# 03_RK3399_Power.net
KiCad netlist of a schematic drawn in Altium Designer
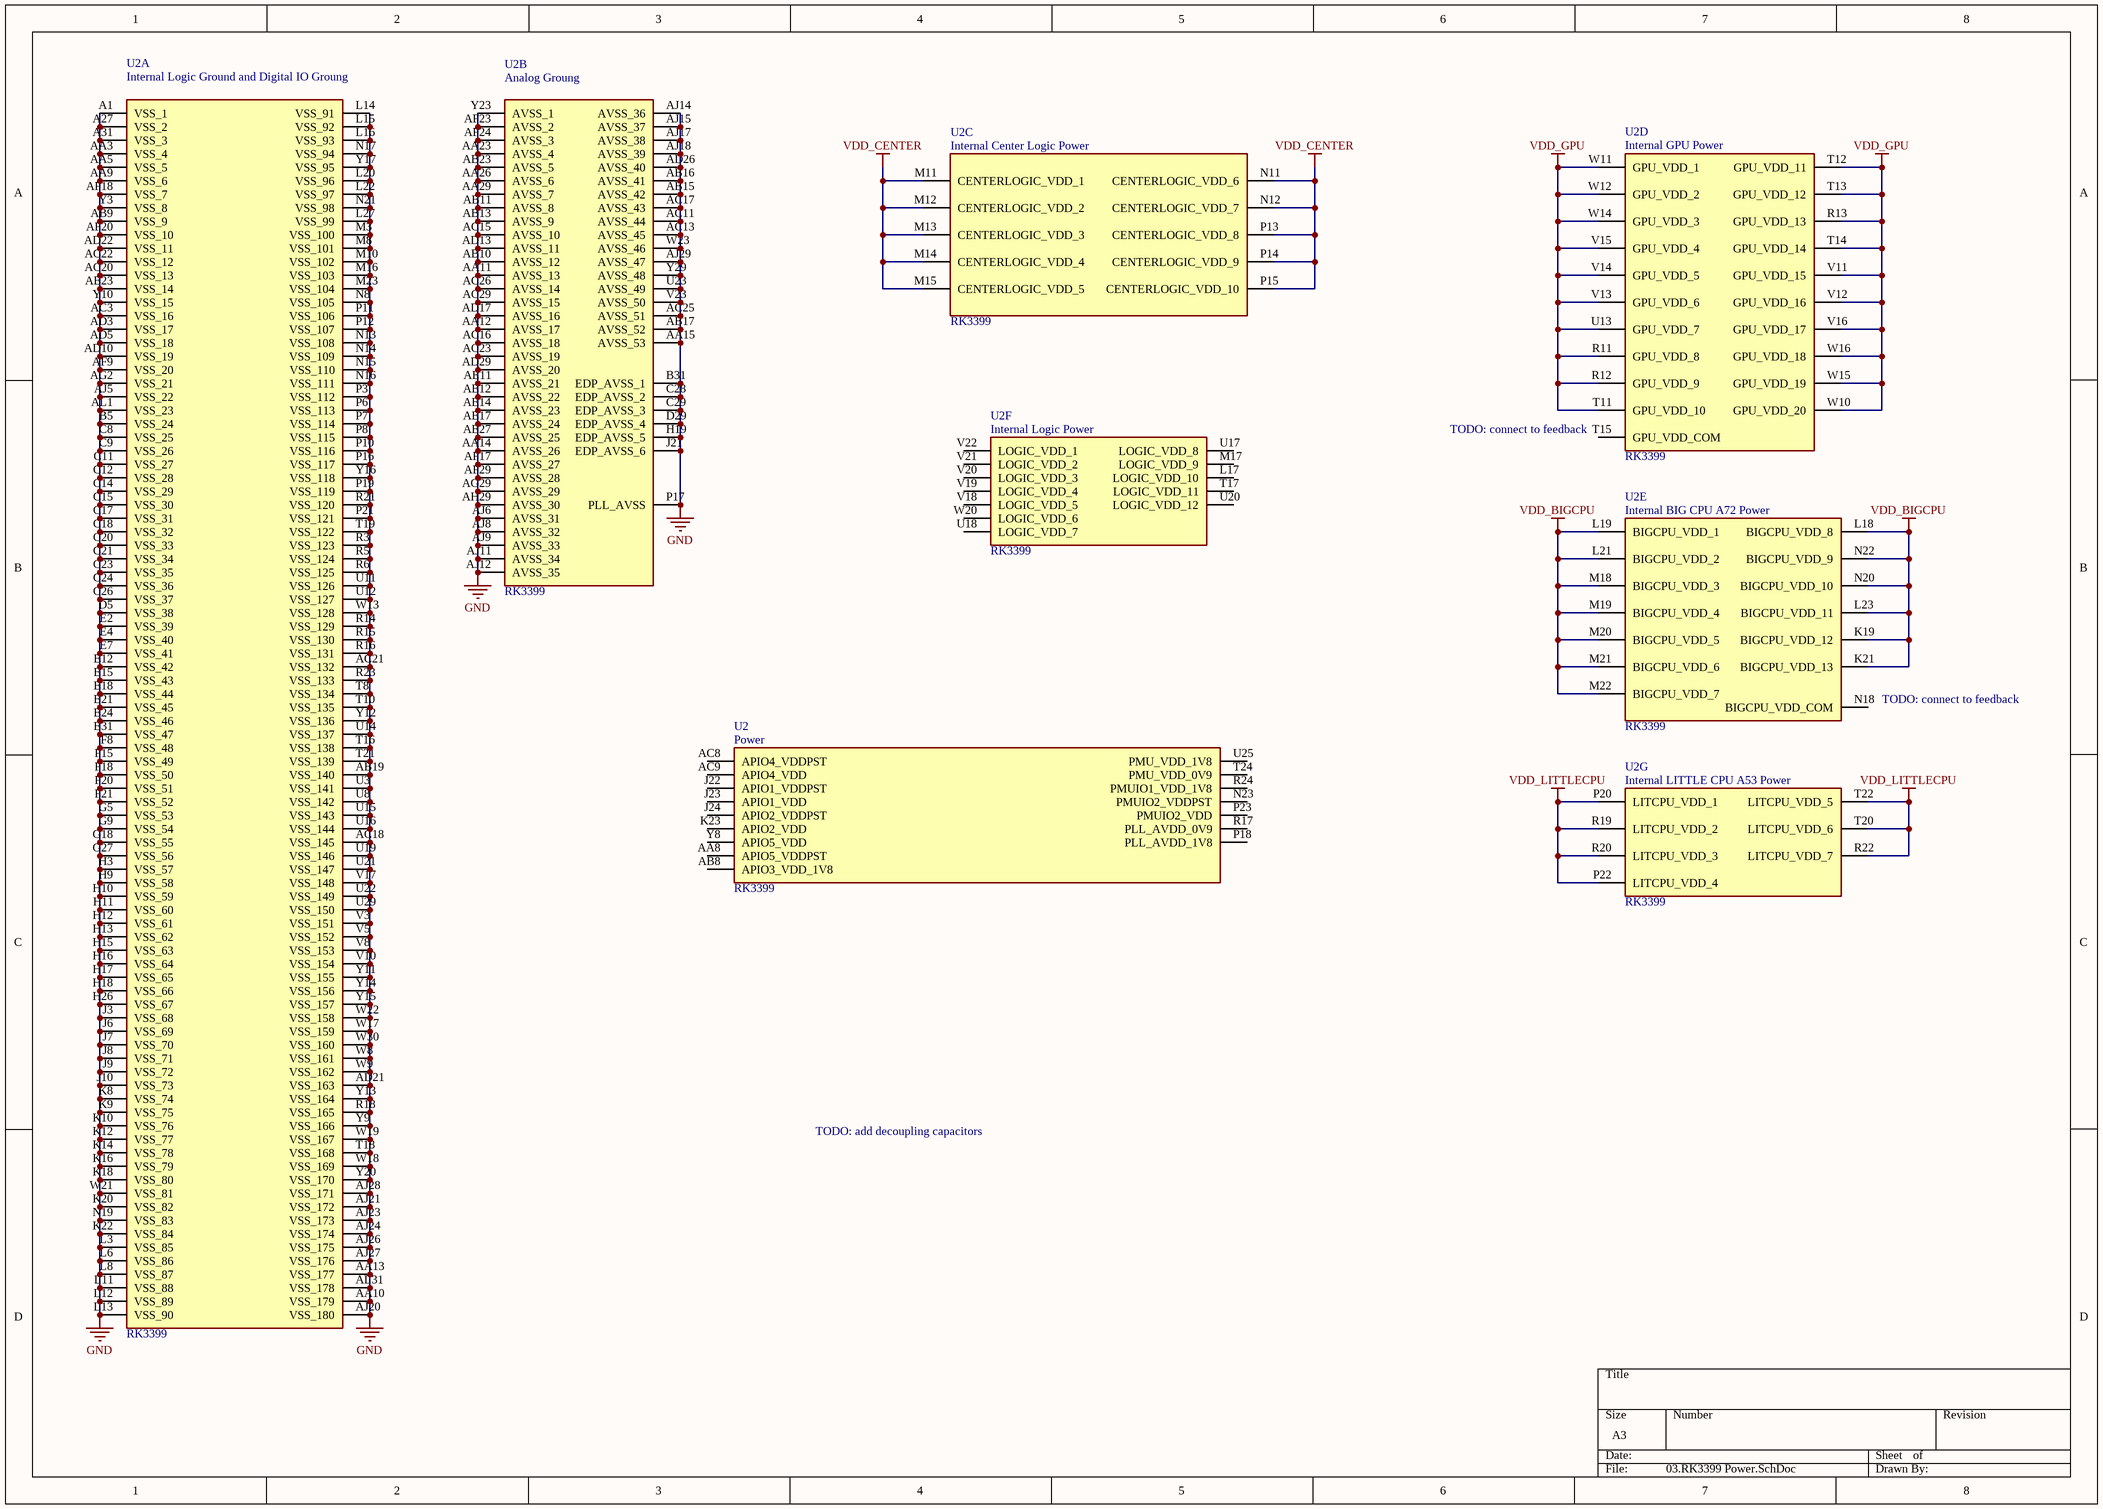
[diagram p0: 03.RK3399 Power.SchDoc]

(export (version "E")
  (design (tool "Eeschema 10.0.6"))
  (components
    (comp (ref "U2")
      (value "RK3399")
      (footprint "BGA828C65P31X31_2100X2100X161N")
      (description "RK3399 ROCK Pi 4 Model A 2GB - ARMÂ® CortexÂ®-A53, CortexÂ®-A72 MPU Embedded Evaluation Board")
      (fields (field (name "MF") "Rockchip"))
      (libsource (lib "RK3399") (part "RK3399"))
    )
  )
  (nets
    (net (code "1") (name "GND") (class "Default")
      (node (ref "U2") (pin "A1") (pinfunction "VSS_1_A1") (pintype "power_in"))
      (node (ref "U2") (pin "A27") (pinfunction "VSS_2_A27") (pintype "power_in"))
      (node (ref "U2") (pin "A31") (pinfunction "VSS_3_A31") (pintype "power_in"))
      (node (ref "U2") (pin "AA10") (pinfunction "VSS_179_AA10") (pintype "power_in"))
      (node (ref "U2") (pin "AA11") (pinfunction "AVSS_13_AA11") (pintype "power_in"))
      (node (ref "U2") (pin "AA12") (pinfunction "AVSS_17_AA12") (pintype "power_in"))
      (node (ref "U2") (pin "AA13") (pinfunction "VSS_177_AA13") (pintype "power_in"))
      (node (ref "U2") (pin "AA14") (pinfunction "AVSS_26_AA14") (pintype "power_in"))
      (node (ref "U2") (pin "AA15") (pinfunction "AVSS_53_AA15") (pintype "power_in"))
      (node (ref "U2") (pin "AA23") (pinfunction "AVSS_4_AA23") (pintype "power_in"))
      (node (ref "U2") (pin "AA26") (pinfunction "AVSS_6_AA26") (pintype "power_in"))
      (node (ref "U2") (pin "AA29") (pinfunction "AVSS_7_AA29") (pintype "power_in"))
      (node (ref "U2") (pin "AA3") (pinfunction "VSS_4_AA3") (pintype "power_in"))
      (node (ref "U2") (pin "AA5") (pinfunction "VSS_5_AA5") (pintype "power_in"))
      (node (ref "U2") (pin "AA9") (pinfunction "VSS_6_AA9") (pintype "power_in"))
      (node (ref "U2") (pin "AB10") (pinfunction "AVSS_12_AB10") (pintype "power_in"))
      (node (ref "U2") (pin "AB11") (pinfunction "AVSS_8_AB11") (pintype "power_in"))
      (node (ref "U2") (pin "AB13") (pinfunction "AVSS_9_AB13") (pintype "power_in"))
      (node (ref "U2") (pin "AB15") (pinfunction "AVSS_42_AB15") (pintype "power_in"))
      (node (ref "U2") (pin "AB16") (pinfunction "AVSS_41_AB16") (pintype "power_in"))
      (node (ref "U2") (pin "AB17") (pinfunction "AVSS_52_AB17") (pintype "power_in"))
      (node (ref "U2") (pin "AB19") (pinfunction "VSS_140_AB19") (pintype "power_in"))
      (node (ref "U2") (pin "AB23") (pinfunction "AVSS_5_AB23") (pintype "power_in"))
      (node (ref "U2") (pin "AB9") (pinfunction "VSS_9_AB9") (pintype "power_in"))
      (node (ref "U2") (pin "AC11") (pinfunction "AVSS_44_AC11") (pintype "power_in"))
      (node (ref "U2") (pin "AC13") (pinfunction "AVSS_45_AC13") (pintype "power_in"))
      (node (ref "U2") (pin "AC15") (pinfunction "AVSS_10_AC15") (pintype "power_in"))
      (node (ref "U2") (pin "AC16") (pinfunction "AVSS_18_AC16") (pintype "power_in"))
      (node (ref "U2") (pin "AC17") (pinfunction "AVSS_43_AC17") (pintype "power_in"))
      (node (ref "U2") (pin "AC18") (pinfunction "VSS_145_AC18") (pintype "power_in"))
      (node (ref "U2") (pin "AC20") (pinfunction "VSS_13_AC20") (pintype "power_in"))
      (node (ref "U2") (pin "AC21") (pinfunction "VSS_132_AC21") (pintype "power_in"))
      (node (ref "U2") (pin "AC22") (pinfunction "VSS_12_AC22") (pintype "power_in"))
      (node (ref "U2") (pin "AC23") (pinfunction "AVSS_19_AC23") (pintype "power_in"))
      (node (ref "U2") (pin "AC25") (pinfunction "AVSS_51_AC25") (pintype "power_in"))
      (node (ref "U2") (pin "AC26") (pinfunction "AVSS_14_AC26") (pintype "power_in"))
      (node (ref "U2") (pin "AC29") (pinfunction "AVSS_15_AC29") (pintype "power_in"))
      (node (ref "U2") (pin "AC3") (pinfunction "VSS_16_AC3") (pintype "power_in"))
      (node (ref "U2") (pin "AD10") (pinfunction "VSS_19_AD10") (pintype "power_in"))
      (node (ref "U2") (pin "AD13") (pinfunction "AVSS_11_AD13") (pintype "power_in"))
      (node (ref "U2") (pin "AD17") (pinfunction "AVSS_16_AD17") (pintype "power_in"))
      (node (ref "U2") (pin "AD21") (pinfunction "VSS_163_AD21") (pintype "power_in"))
      (node (ref "U2") (pin "AD22") (pinfunction "VSS_11_AD22") (pintype "power_in"))
      (node (ref "U2") (pin "AD26") (pinfunction "AVSS_40_AD26") (pintype "power_in"))
      (node (ref "U2") (pin "AD29") (pinfunction "AVSS_20_AD29") (pintype "power_in"))
      (node (ref "U2") (pin "AD3") (pinfunction "VSS_17_AD3") (pintype "power_in"))
      (node (ref "U2") (pin "AD5") (pinfunction "VSS_18_AD5") (pintype "power_in"))
      (node (ref "U2") (pin "AE11") (pinfunction "AVSS_21_AE11") (pintype "power_in"))
      (node (ref "U2") (pin "AE12") (pinfunction "AVSS_22_AE12") (pintype "power_in"))
      (node (ref "U2") (pin "AE14") (pinfunction "AVSS_23_AE14") (pintype "power_in"))
      (node (ref "U2") (pin "AE17") (pinfunction "AVSS_24_AE17") (pintype "power_in"))
      (node (ref "U2") (pin "AE23") (pinfunction "VSS_14_AE23") (pintype "power_in"))
      (node (ref "U2") (pin "AE27") (pinfunction "AVSS_25_AE27") (pintype "power_in"))
      (node (ref "U2") (pin "AF17") (pinfunction "AVSS_27_AF17") (pintype "power_in"))
      (node (ref "U2") (pin "AF18") (pinfunction "VSS_7_AF18") (pintype "power_in"))
      (node (ref "U2") (pin "AF20") (pinfunction "VSS_10_AF20") (pintype "power_in"))
      (node (ref "U2") (pin "AF23") (pinfunction "AVSS_2_AF23") (pintype "power_in"))
      (node (ref "U2") (pin "AF24") (pinfunction "AVSS_3_AF24") (pintype "power_in"))
      (node (ref "U2") (pin "AF29") (pinfunction "AVSS_28_AF29") (pintype "power_in"))
      (node (ref "U2") (pin "AF9") (pinfunction "VSS_20_AF9") (pintype "power_in"))
      (node (ref "U2") (pin "AG2") (pinfunction "VSS_21_AG2") (pintype "power_in"))
      (node (ref "U2") (pin "AG29") (pinfunction "AVSS_29_AG29") (pintype "power_in"))
      (node (ref "U2") (pin "AH29") (pinfunction "AVSS_30_AH29") (pintype "power_in"))
      (node (ref "U2") (pin "AJ11") (pinfunction "AVSS_34_AJ11") (pintype "power_in"))
      (node (ref "U2") (pin "AJ12") (pinfunction "AVSS_35_AJ12") (pintype "power_in"))
      (node (ref "U2") (pin "AJ14") (pinfunction "AVSS_36_AJ14") (pintype "power_in"))
      (node (ref "U2") (pin "AJ15") (pinfunction "AVSS_37_AJ15") (pintype "power_in"))
      (node (ref "U2") (pin "AJ17") (pinfunction "AVSS_38_AJ17") (pintype "power_in"))
      (node (ref "U2") (pin "AJ18") (pinfunction "AVSS_39_AJ18") (pintype "power_in"))
      (node (ref "U2") (pin "AJ20") (pinfunction "VSS_180_AJ20") (pintype "power_in"))
      (node (ref "U2") (pin "AJ21") (pinfunction "VSS_172_AJ21") (pintype "power_in"))
      (node (ref "U2") (pin "AJ23") (pinfunction "VSS_173_AJ23") (pintype "power_in"))
      (node (ref "U2") (pin "AJ24") (pinfunction "VSS_174_AJ24") (pintype "power_in"))
      (node (ref "U2") (pin "AJ26") (pinfunction "VSS_175_AJ26") (pintype "power_in"))
      (node (ref "U2") (pin "AJ27") (pinfunction "VSS_176_AJ27") (pintype "power_in"))
      (node (ref "U2") (pin "AJ28") (pinfunction "VSS_171_AJ28") (pintype "power_in"))
      (node (ref "U2") (pin "AJ29") (pinfunction "AVSS_47_AJ29") (pintype "power_in"))
      (node (ref "U2") (pin "AJ5") (pinfunction "VSS_22_AJ5") (pintype "power_in"))
      (node (ref "U2") (pin "AJ6") (pinfunction "AVSS_31_AJ6") (pintype "power_in"))
      (node (ref "U2") (pin "AJ8") (pinfunction "AVSS_32_AJ8") (pintype "power_in"))
      (node (ref "U2") (pin "AJ9") (pinfunction "AVSS_33_AJ9") (pintype "power_in"))
      (node (ref "U2") (pin "AL1") (pinfunction "VSS_23_AL1") (pintype "power_in"))
      (node (ref "U2") (pin "AL31") (pinfunction "VSS_178_AL31") (pintype "power_in"))
      (node (ref "U2") (pin "B31") (pinfunction "EDP_AVSS_1_B31") (pintype "power_in"))
      (node (ref "U2") (pin "B5") (pinfunction "VSS_24_B5") (pintype "power_in"))
      (node (ref "U2") (pin "C11") (pinfunction "VSS_27_C11") (pintype "power_in"))
      (node (ref "U2") (pin "C12") (pinfunction "VSS_28_C12") (pintype "power_in"))
      (node (ref "U2") (pin "C14") (pinfunction "VSS_29_C14") (pintype "power_in"))
      (node (ref "U2") (pin "C15") (pinfunction "VSS_30_C15") (pintype "power_in"))
      (node (ref "U2") (pin "C17") (pinfunction "VSS_31_C17") (pintype "power_in"))
      (node (ref "U2") (pin "C18") (pinfunction "VSS_32_C18") (pintype "power_in"))
      (node (ref "U2") (pin "C20") (pinfunction "VSS_33_C20") (pintype "power_in"))
      (node (ref "U2") (pin "C21") (pinfunction "VSS_34_C21") (pintype "power_in"))
      (node (ref "U2") (pin "C23") (pinfunction "VSS_35_C23") (pintype "power_in"))
      (node (ref "U2") (pin "C24") (pinfunction "VSS_36_C24") (pintype "power_in"))
      (node (ref "U2") (pin "C26") (pinfunction "VSS_37_C26") (pintype "power_in"))
      (node (ref "U2") (pin "C28") (pinfunction "EDP_AVSS_2_C28") (pintype "power_in"))
      (node (ref "U2") (pin "C29") (pinfunction "EDP_AVSS_3_C29") (pintype "power_in"))
      (node (ref "U2") (pin "C8") (pinfunction "VSS_25_C8") (pintype "power_in"))
      (node (ref "U2") (pin "C9") (pinfunction "VSS_26_C9") (pintype "power_in"))
      (node (ref "U2") (pin "D29") (pinfunction "EDP_AVSS_4_D29") (pintype "power_in"))
      (node (ref "U2") (pin "D5") (pinfunction "VSS_38_D5") (pintype "power_in"))
      (node (ref "U2") (pin "E12") (pinfunction "VSS_42_E12") (pintype "power_in"))
      (node (ref "U2") (pin "E15") (pinfunction "VSS_43_E15") (pintype "power_in"))
      (node (ref "U2") (pin "E18") (pinfunction "VSS_44_E18") (pintype "power_in"))
      (node (ref "U2") (pin "E2") (pinfunction "VSS_39_E2") (pintype "power_in"))
      (node (ref "U2") (pin "E21") (pinfunction "VSS_45_E21") (pintype "power_in"))
      (node (ref "U2") (pin "E24") (pinfunction "VSS_46_E24") (pintype "power_in"))
      (node (ref "U2") (pin "E31") (pinfunction "VSS_47_E31") (pintype "power_in"))
      (node (ref "U2") (pin "E4") (pinfunction "VSS_40_E4") (pintype "power_in"))
      (node (ref "U2") (pin "E7") (pinfunction "VSS_41_E7") (pintype "power_in"))
      (node (ref "U2") (pin "F15") (pinfunction "VSS_49_F15") (pintype "power_in"))
      (node (ref "U2") (pin "F18") (pinfunction "VSS_50_F18") (pintype "power_in"))
      (node (ref "U2") (pin "F20") (pinfunction "VSS_51_F20") (pintype "power_in"))
      (node (ref "U2") (pin "F21") (pinfunction "VSS_52_F21") (pintype "power_in"))
      (node (ref "U2") (pin "F8") (pinfunction "VSS_48_F8") (pintype "power_in"))
      (node (ref "U2") (pin "G18") (pinfunction "VSS_55_G18") (pintype "power_in"))
      (node (ref "U2") (pin "G27") (pinfunction "VSS_56_G27") (pintype "power_in"))
      (node (ref "U2") (pin "G5") (pinfunction "VSS_53_G5") (pintype "power_in"))
      (node (ref "U2") (pin "G9") (pinfunction "VSS_54_G9") (pintype "power_in"))
      (node (ref "U2") (pin "H10") (pinfunction "VSS_59_H10") (pintype "power_in"))
      (node (ref "U2") (pin "H11") (pinfunction "VSS_60_H11") (pintype "power_in"))
      (node (ref "U2") (pin "H12") (pinfunction "VSS_61_H12") (pintype "power_in"))
      (node (ref "U2") (pin "H13") (pinfunction "VSS_62_H13") (pintype "power_in"))
      (node (ref "U2") (pin "H15") (pinfunction "VSS_63_H15") (pintype "power_in"))
      (node (ref "U2") (pin "H16") (pinfunction "VSS_64_H16") (pintype "power_in"))
      (node (ref "U2") (pin "H17") (pinfunction "VSS_65_H17") (pintype "power_in"))
      (node (ref "U2") (pin "H18") (pinfunction "VSS_66_H18") (pintype "power_in"))
      (node (ref "U2") (pin "H19") (pinfunction "EDP_AVSS_5_H19") (pintype "power_in"))
      (node (ref "U2") (pin "H26") (pinfunction "VSS_67_H26") (pintype "power_in"))
      (node (ref "U2") (pin "H3") (pinfunction "VSS_57_H3") (pintype "power_in"))
      (node (ref "U2") (pin "H9") (pinfunction "VSS_58_H9") (pintype "power_in"))
      (node (ref "U2") (pin "J10") (pinfunction "VSS_73_J10") (pintype "power_in"))
      (node (ref "U2") (pin "J21") (pinfunction "EDP_AVSS_6_J21") (pintype "power_in"))
      (node (ref "U2") (pin "J3") (pinfunction "VSS_68_J3") (pintype "power_in"))
      (node (ref "U2") (pin "J6") (pinfunction "VSS_69_J6") (pintype "power_in"))
      (node (ref "U2") (pin "J7") (pinfunction "VSS_70_J7") (pintype "power_in"))
      (node (ref "U2") (pin "J8") (pinfunction "VSS_71_J8") (pintype "power_in"))
      (node (ref "U2") (pin "J9") (pinfunction "VSS_72_J9") (pintype "power_in"))
      (node (ref "U2") (pin "K10") (pinfunction "VSS_76_K10") (pintype "power_in"))
      (node (ref "U2") (pin "K12") (pinfunction "VSS_77_K12") (pintype "power_in"))
      (node (ref "U2") (pin "K14") (pinfunction "VSS_78_K14") (pintype "power_in"))
      (node (ref "U2") (pin "K16") (pinfunction "VSS_79_K16") (pintype "power_in"))
      (node (ref "U2") (pin "K18") (pinfunction "VSS_80_K18") (pintype "power_in"))
      (node (ref "U2") (pin "K20") (pinfunction "VSS_82_K20") (pintype "power_in"))
      (node (ref "U2") (pin "K22") (pinfunction "VSS_84_K22") (pintype "power_in"))
      (node (ref "U2") (pin "K8") (pinfunction "VSS_74_K8") (pintype "power_in"))
      (node (ref "U2") (pin "K9") (pinfunction "VSS_75_K9") (pintype "power_in"))
      (node (ref "U2") (pin "L11") (pinfunction "VSS_88_L11") (pintype "power_in"))
      (node (ref "U2") (pin "L12") (pinfunction "VSS_89_L12") (pintype "power_in"))
      (node (ref "U2") (pin "L13") (pinfunction "VSS_90_L13") (pintype "power_in"))
      (node (ref "U2") (pin "L14") (pinfunction "VSS_91_L14") (pintype "power_in"))
      (node (ref "U2") (pin "L15") (pinfunction "VSS_92_L15") (pintype "power_in"))
      (node (ref "U2") (pin "L16") (pinfunction "VSS_93_L16") (pintype "power_in"))
      (node (ref "U2") (pin "L20") (pinfunction "VSS_96_L20") (pintype "power_in"))
      (node (ref "U2") (pin "L22") (pinfunction "VSS_97_L22") (pintype "power_in"))
      (node (ref "U2") (pin "L27") (pinfunction "VSS_99_L27") (pintype "power_in"))
      (node (ref "U2") (pin "L3") (pinfunction "VSS_85_L3") (pintype "power_in"))
      (node (ref "U2") (pin "L6") (pinfunction "VSS_86_L6") (pintype "power_in"))
      (node (ref "U2") (pin "L8") (pinfunction "VSS_87_L8") (pintype "power_in"))
      (node (ref "U2") (pin "M10") (pinfunction "VSS_102_M10") (pintype "power_in"))
      (node (ref "U2") (pin "M16") (pinfunction "VSS_103_M16") (pintype "power_in"))
      (node (ref "U2") (pin "M23") (pinfunction "VSS_104_M23") (pintype "power_in"))
      (node (ref "U2") (pin "M3") (pinfunction "VSS_100_M3") (pintype "power_in"))
      (node (ref "U2") (pin "M8") (pinfunction "VSS_101_M8") (pintype "power_in"))
      (node (ref "U2") (pin "N13") (pinfunction "VSS_108_N13") (pintype "power_in"))
      (node (ref "U2") (pin "N14") (pinfunction "VSS_109_N14") (pintype "power_in"))
      (node (ref "U2") (pin "N15") (pinfunction "VSS_110_N15") (pintype "power_in"))
      (node (ref "U2") (pin "N16") (pinfunction "VSS_111_N16") (pintype "power_in"))
      (node (ref "U2") (pin "N17") (pinfunction "VSS_94_N17") (pintype "power_in"))
      (node (ref "U2") (pin "N19") (pinfunction "VSS_83_N19") (pintype "power_in"))
      (node (ref "U2") (pin "N21") (pinfunction "VSS_98_N21") (pintype "power_in"))
      (node (ref "U2") (pin "N8") (pinfunction "VSS_105_N8") (pintype "power_in"))
      (node (ref "U2") (pin "P10") (pinfunction "VSS_116_P10") (pintype "power_in"))
      (node (ref "U2") (pin "P11") (pinfunction "VSS_106_P11") (pintype "power_in"))
      (node (ref "U2") (pin "P12") (pinfunction "VSS_107_P12") (pintype "power_in"))
      (node (ref "U2") (pin "P16") (pinfunction "VSS_117_P16") (pintype "power_in"))
      (node (ref "U2") (pin "P17") (pinfunction "PLL_AVSS_P17") (pintype "power_in"))
      (node (ref "U2") (pin "P19") (pinfunction "VSS_119_P19") (pintype "power_in"))
      (node (ref "U2") (pin "P21") (pinfunction "VSS_121_P21") (pintype "power_in"))
      (node (ref "U2") (pin "P3") (pinfunction "VSS_112_P3") (pintype "power_in"))
      (node (ref "U2") (pin "P6") (pinfunction "VSS_113_P6") (pintype "power_in"))
      (node (ref "U2") (pin "P7") (pinfunction "VSS_114_P7") (pintype "power_in"))
      (node (ref "U2") (pin "P8") (pinfunction "VSS_115_P8") (pintype "power_in"))
      (node (ref "U2") (pin "R14") (pinfunction "VSS_129_R14") (pintype "power_in"))
      (node (ref "U2") (pin "R15") (pinfunction "VSS_130_R15") (pintype "power_in"))
      (node (ref "U2") (pin "R16") (pinfunction "VSS_131_R16") (pintype "power_in"))
      (node (ref "U2") (pin "R18") (pinfunction "VSS_165_R18") (pintype "power_in"))
      (node (ref "U2") (pin "R21") (pinfunction "VSS_120_R21") (pintype "power_in"))
      (node (ref "U2") (pin "R23") (pinfunction "VSS_133_R23") (pintype "power_in"))
      (node (ref "U2") (pin "R3") (pinfunction "VSS_123_R3") (pintype "power_in"))
      (node (ref "U2") (pin "R5") (pinfunction "VSS_124_R5") (pintype "power_in"))
      (node (ref "U2") (pin "R6") (pinfunction "VSS_125_R6") (pintype "power_in"))
      (node (ref "U2") (pin "T10") (pinfunction "VSS_135_T10") (pintype "power_in"))
      (node (ref "U2") (pin "T16") (pinfunction "VSS_138_T16") (pintype "power_in"))
      (node (ref "U2") (pin "T18") (pinfunction "VSS_168_T18") (pintype "power_in"))
      (node (ref "U2") (pin "T19") (pinfunction "VSS_122_T19") (pintype "power_in"))
      (node (ref "U2") (pin "T21") (pinfunction "VSS_139_T21") (pintype "power_in"))
      (node (ref "U2") (pin "T8") (pinfunction "VSS_134_T8") (pintype "power_in"))
      (node (ref "U2") (pin "U11") (pinfunction "VSS_126_U11") (pintype "power_in"))
      (node (ref "U2") (pin "U12") (pinfunction "VSS_127_U12") (pintype "power_in"))
      (node (ref "U2") (pin "U14") (pinfunction "VSS_137_U14") (pintype "power_in"))
      (node (ref "U2") (pin "U15") (pinfunction "VSS_143_U15") (pintype "power_in"))
      (node (ref "U2") (pin "U16") (pinfunction "VSS_144_U16") (pintype "power_in"))
      (node (ref "U2") (pin "U19") (pinfunction "VSS_146_U19") (pintype "power_in"))
      (node (ref "U2") (pin "U21") (pinfunction "VSS_147_U21") (pintype "power_in"))
      (node (ref "U2") (pin "U22") (pinfunction "VSS_149_U22") (pintype "power_in"))
      (node (ref "U2") (pin "U23") (pinfunction "AVSS_49_U23") (pintype "power_in"))
      (node (ref "U2") (pin "U29") (pinfunction "VSS_150_U29") (pintype "power_in"))
      (node (ref "U2") (pin "U3") (pinfunction "VSS_141_U3") (pintype "power_in"))
      (node (ref "U2") (pin "U8") (pinfunction "VSS_142_U8") (pintype "power_in"))
      (node (ref "U2") (pin "V10") (pinfunction "VSS_154_V10") (pintype "power_in"))
      (node (ref "U2") (pin "V17") (pinfunction "VSS_148_V17") (pintype "power_in"))
      (node (ref "U2") (pin "V23") (pinfunction "AVSS_50_V23") (pintype "power_in"))
      (node (ref "U2") (pin "V3") (pinfunction "VSS_151_V3") (pintype "power_in"))
      (node (ref "U2") (pin "V5") (pinfunction "VSS_152_V5") (pintype "power_in"))
      (node (ref "U2") (pin "V8") (pinfunction "VSS_153_V8") (pintype "power_in"))
      (node (ref "U2") (pin "W13") (pinfunction "VSS_128_W13") (pintype "power_in"))
      (node (ref "U2") (pin "W17") (pinfunction "VSS_159_W17") (pintype "power_in"))
      (node (ref "U2") (pin "W18") (pinfunction "VSS_169_W18") (pintype "power_in"))
      (node (ref "U2") (pin "W19") (pinfunction "VSS_167_W19") (pintype "power_in"))
      (node (ref "U2") (pin "W21") (pinfunction "VSS_81_W21") (pintype "power_in"))
      (node (ref "U2") (pin "W22") (pinfunction "VSS_158_W22") (pintype "power_in"))
      (node (ref "U2") (pin "W23") (pinfunction "AVSS_46_W23") (pintype "power_in"))
      (node (ref "U2") (pin "W30") (pinfunction "VSS_160_W30") (pintype "power_in"))
      (node (ref "U2") (pin "W8") (pinfunction "VSS_161_W8") (pintype "power_in"))
      (node (ref "U2") (pin "W9") (pinfunction "VSS_162_W9") (pintype "power_in"))
      (node (ref "U2") (pin "Y10") (pinfunction "VSS_15_Y10") (pintype "power_in"))
      (node (ref "U2") (pin "Y11") (pinfunction "VSS_155_Y11") (pintype "power_in"))
      (node (ref "U2") (pin "Y12") (pinfunction "VSS_136_Y12") (pintype "power_in"))
      (node (ref "U2") (pin "Y13") (pinfunction "VSS_164_Y13") (pintype "power_in"))
      (node (ref "U2") (pin "Y14") (pinfunction "VSS_156_Y14") (pintype "power_in"))
      (node (ref "U2") (pin "Y15") (pinfunction "VSS_157_Y15") (pintype "power_in"))
      (node (ref "U2") (pin "Y16") (pinfunction "VSS_118_Y16") (pintype "power_in"))
      (node (ref "U2") (pin "Y17") (pinfunction "VSS_95_Y17") (pintype "power_in"))
      (node (ref "U2") (pin "Y20") (pinfunction "VSS_170_Y20") (pintype "power_in"))
      (node (ref "U2") (pin "Y23") (pinfunction "AVSS_1_Y23") (pintype "power_in"))
      (node (ref "U2") (pin "Y29") (pinfunction "AVSS_48_Y29") (pintype "power_in"))
      (node (ref "U2") (pin "Y3") (pinfunction "VSS_8_Y3") (pintype "power_in"))
      (node (ref "U2") (pin "Y9") (pinfunction "VSS_166_Y9") (pintype "power_in"))
    )
    (net (code "2") (name "VDD_BIGCPU") (class "Default")
      (node (ref "U2") (pin "K19") (pinfunction "BIGCPU_VDD_12_K19") (pintype "power_in"))
      (node (ref "U2") (pin "K21") (pinfunction "BIGCPU_VDD_13_K21") (pintype "power_in"))
      (node (ref "U2") (pin "L18") (pinfunction "BIGCPU_VDD_8_L18") (pintype "power_in"))
      (node (ref "U2") (pin "L19") (pinfunction "BIGCPU_VDD_1_L19") (pintype "power_in"))
      (node (ref "U2") (pin "L21") (pinfunction "BIGCPU_VDD_2_L21") (pintype "power_in"))
      (node (ref "U2") (pin "L23") (pinfunction "BIGCPU_VDD_11_L23") (pintype "power_in"))
      (node (ref "U2") (pin "M18") (pinfunction "BIGCPU_VDD_3_M18") (pintype "power_in"))
      (node (ref "U2") (pin "M19") (pinfunction "BIGCPU_VDD_4_M19") (pintype "power_in"))
      (node (ref "U2") (pin "M20") (pinfunction "BIGCPU_VDD_5_M20") (pintype "power_in"))
      (node (ref "U2") (pin "M21") (pinfunction "BIGCPU_VDD_6_M21") (pintype "power_in"))
      (node (ref "U2") (pin "M22") (pinfunction "BIGCPU_VDD_7_M22") (pintype "power_in"))
      (node (ref "U2") (pin "N20") (pinfunction "BIGCPU_VDD_10_N20") (pintype "power_in"))
      (node (ref "U2") (pin "N22") (pinfunction "BIGCPU_VDD_9_N22") (pintype "power_in"))
    )
    (net (code "3") (name "VDD_CENTER") (class "Default")
      (node (ref "U2") (pin "M11") (pinfunction "CENTERLOGIC_VDD_1_M11") (pintype "power_in"))
      (node (ref "U2") (pin "M12") (pinfunction "CENTERLOGIC_VDD_2_M12") (pintype "power_in"))
      (node (ref "U2") (pin "M13") (pinfunction "CENTERLOGIC_VDD_3_M13") (pintype "power_in"))
      (node (ref "U2") (pin "M14") (pinfunction "CENTERLOGIC_VDD_4_M14") (pintype "power_in"))
      (node (ref "U2") (pin "M15") (pinfunction "CENTERLOGIC_VDD_5_M15") (pintype "power_in"))
      (node (ref "U2") (pin "N11") (pinfunction "CENTERLOGIC_VDD_6_N11") (pintype "power_in"))
      (node (ref "U2") (pin "N12") (pinfunction "CENTERLOGIC_VDD_7_N12") (pintype "power_in"))
      (node (ref "U2") (pin "P13") (pinfunction "CENTERLOGIC_VDD_8_P13") (pintype "power_in"))
      (node (ref "U2") (pin "P14") (pinfunction "CENTERLOGIC_VDD_9_P14") (pintype "power_in"))
      (node (ref "U2") (pin "P15") (pinfunction "CENTERLOGIC_VDD_10_P15") (pintype "power_in"))
    )
    (net (code "4") (name "VDD_GPU") (class "Default")
      (node (ref "U2") (pin "R11") (pinfunction "GPU_VDD_8_R11") (pintype "power_in"))
      (node (ref "U2") (pin "R12") (pinfunction "GPU_VDD_9_R12") (pintype "power_in"))
      (node (ref "U2") (pin "R13") (pinfunction "GPU_VDD_13_R13") (pintype "power_in"))
      (node (ref "U2") (pin "T11") (pinfunction "GPU_VDD_10_T11") (pintype "power_in"))
      (node (ref "U2") (pin "T12") (pinfunction "GPU_VDD_11_T12") (pintype "power_in"))
      (node (ref "U2") (pin "T13") (pinfunction "GPU_VDD_12_T13") (pintype "power_in"))
      (node (ref "U2") (pin "T14") (pinfunction "GPU_VDD_14_T14") (pintype "power_in"))
      (node (ref "U2") (pin "U13") (pinfunction "GPU_VDD_7_U13") (pintype "power_in"))
      (node (ref "U2") (pin "V11") (pinfunction "GPU_VDD_15_V11") (pintype "power_in"))
      (node (ref "U2") (pin "V12") (pinfunction "GPU_VDD_16_V12") (pintype "power_in"))
      (node (ref "U2") (pin "V13") (pinfunction "GPU_VDD_6_V13") (pintype "power_in"))
      (node (ref "U2") (pin "V14") (pinfunction "GPU_VDD_5_V14") (pintype "power_in"))
      (node (ref "U2") (pin "V15") (pinfunction "GPU_VDD_4_V15") (pintype "power_in"))
      (node (ref "U2") (pin "V16") (pinfunction "GPU_VDD_17_V16") (pintype "power_in"))
      (node (ref "U2") (pin "W10") (pinfunction "GPU_VDD_20_W10") (pintype "power_in"))
      (node (ref "U2") (pin "W11") (pinfunction "GPU_VDD_1_W11") (pintype "power_in"))
      (node (ref "U2") (pin "W12") (pinfunction "GPU_VDD_2_W12") (pintype "power_in"))
      (node (ref "U2") (pin "W14") (pinfunction "GPU_VDD_3_W14") (pintype "power_in"))
      (node (ref "U2") (pin "W15") (pinfunction "GPU_VDD_19_W15") (pintype "power_in"))
      (node (ref "U2") (pin "W16") (pinfunction "GPU_VDD_18_W16") (pintype "power_in"))
    )
    (net (code "5") (name "VDD_LITTLECPU") (class "Default")
      (node (ref "U2") (pin "P20") (pinfunction "LITCPU_VDD_1_P20") (pintype "power_in"))
      (node (ref "U2") (pin "P22") (pinfunction "LITCPU_VDD_4_P22") (pintype "power_in"))
      (node (ref "U2") (pin "R19") (pinfunction "LITCPU_VDD_2_R19") (pintype "power_in"))
      (node (ref "U2") (pin "R20") (pinfunction "LITCPU_VDD_3_R20") (pintype "power_in"))
      (node (ref "U2") (pin "R22") (pinfunction "LITCPU_VDD_7_R22") (pintype "power_in"))
      (node (ref "U2") (pin "T20") (pinfunction "LITCPU_VDD_6_T20") (pintype "power_in"))
      (node (ref "U2") (pin "T22") (pinfunction "LITCPU_VDD_5_T22") (pintype "power_in"))
    )
    (net (code "6") (name "unconnected-(U2AC-APIO1_VDD-PadJ23)") (class "Default")
      (node (ref "U2") (pin "J23") (pinfunction "APIO1_VDD_J23") (pintype "power_in"))
    )
    (net (code "7") (name "unconnected-(U2AC-APIO1_VDDPST-PadJ22)") (class "Default")
      (node (ref "U2") (pin "J22") (pinfunction "APIO1_VDDPST_J22") (pintype "power_in"))
    )
    (net (code "8") (name "unconnected-(U2AC-APIO2_VDD-PadK23)") (class "Default")
      (node (ref "U2") (pin "K23") (pinfunction "APIO2_VDD_K23") (pintype "power_in"))
    )
    (net (code "9") (name "unconnected-(U2AC-APIO2_VDDPST-PadJ24)") (class "Default")
      (node (ref "U2") (pin "J24") (pinfunction "APIO2_VDDPST_J24") (pintype "power_in"))
    )
    (net (code "10") (name "unconnected-(U2AC-APIO3_VDD_1V8-PadAB8)") (class "Default")
      (node (ref "U2") (pin "AB8") (pinfunction "APIO3_VDD_1V8_AB8") (pintype "power_in"))
    )
    (net (code "11") (name "unconnected-(U2AC-APIO4_VDD-PadAC9)") (class "Default")
      (node (ref "U2") (pin "AC9") (pinfunction "APIO4_VDD_AC9") (pintype "power_in"))
    )
    (net (code "12") (name "unconnected-(U2AC-APIO4_VDDPST-PadAC8)") (class "Default")
      (node (ref "U2") (pin "AC8") (pinfunction "APIO4_VDDPST_AC8") (pintype "power_in"))
    )
    (net (code "13") (name "unconnected-(U2AC-APIO5_VDD-PadY8)") (class "Default")
      (node (ref "U2") (pin "Y8") (pinfunction "APIO5_VDD_Y8") (pintype "power_in"))
    )
    (net (code "14") (name "unconnected-(U2AC-APIO5_VDDPST-PadAA8)") (class "Default")
      (node (ref "U2") (pin "AA8") (pinfunction "APIO5_VDDPST_AA8") (pintype "power_in"))
    )
    (net (code "15") (name "unconnected-(U2AC-PLL_AVDD_0V9-PadR17)") (class "Default")
      (node (ref "U2") (pin "R17") (pinfunction "PLL_AVDD_0V9_R17") (pintype "power_in"))
    )
    (net (code "16") (name "unconnected-(U2AC-PLL_AVDD_1V8-PadP18)") (class "Default")
      (node (ref "U2") (pin "P18") (pinfunction "PLL_AVDD_1V8_P18") (pintype "power_in"))
    )
    (net (code "17") (name "unconnected-(U2AC-PMUIO1_VDD_1V8-PadR24)") (class "Default")
      (node (ref "U2") (pin "R24") (pinfunction "PMUIO1_VDD_1V8_R24") (pintype "power_in"))
    )
    (net (code "18") (name "unconnected-(U2AC-PMUIO2_VDD-PadP23)") (class "Default")
      (node (ref "U2") (pin "P23") (pinfunction "PMUIO2_VDD_P23") (pintype "power_in"))
    )
    (net (code "19") (name "unconnected-(U2AC-PMUIO2_VDDPST-PadN23)") (class "Default")
      (node (ref "U2") (pin "N23") (pinfunction "PMUIO2_VDDPST_N23") (pintype "power_in"))
    )
    (net (code "20") (name "unconnected-(U2AC-PMU_VDD_0V9-PadT24)") (class "Default")
      (node (ref "U2") (pin "T24") (pinfunction "PMU_VDD_0V9_T24") (pintype "power_in"))
    )
    (net (code "21") (name "unconnected-(U2AC-PMU_VDD_1V8-PadU25)") (class "Default")
      (node (ref "U2") (pin "U25") (pinfunction "PMU_VDD_1V8_U25") (pintype "power_in"))
    )
    (net (code "22") (name "unconnected-(U2D-GPU_VDD_COM-PadT15)") (class "Default")
      (node (ref "U2") (pin "T15") (pinfunction "GPU_VDD_COM_T15") (pintype "power_in"))
    )
    (net (code "23") (name "unconnected-(U2E-BIGCPU_VDD_COM-PadN18)") (class "Default")
      (node (ref "U2") (pin "N18") (pinfunction "BIGCPU_VDD_COM_N18") (pintype "power_in"))
    )
    (net (code "24") (name "unconnected-(U2F-LOGIC_VDD_1-PadV22)") (class "Default")
      (node (ref "U2") (pin "V22") (pinfunction "LOGIC_VDD_1_V22") (pintype "power_in"))
    )
    (net (code "25") (name "unconnected-(U2F-LOGIC_VDD_2-PadV21)") (class "Default")
      (node (ref "U2") (pin "V21") (pinfunction "LOGIC_VDD_2_V21") (pintype "power_in"))
    )
    (net (code "26") (name "unconnected-(U2F-LOGIC_VDD_3-PadV20)") (class "Default")
      (node (ref "U2") (pin "V20") (pinfunction "LOGIC_VDD_3_V20") (pintype "power_in"))
    )
    (net (code "27") (name "unconnected-(U2F-LOGIC_VDD_4-PadV19)") (class "Default")
      (node (ref "U2") (pin "V19") (pinfunction "LOGIC_VDD_4_V19") (pintype "power_in"))
    )
    (net (code "28") (name "unconnected-(U2F-LOGIC_VDD_5-PadV18)") (class "Default")
      (node (ref "U2") (pin "V18") (pinfunction "LOGIC_VDD_5_V18") (pintype "power_in"))
    )
    (net (code "29") (name "unconnected-(U2F-LOGIC_VDD_6-PadW20)") (class "Default")
      (node (ref "U2") (pin "W20") (pinfunction "LOGIC_VDD_6_W20") (pintype "power_in"))
    )
    (net (code "30") (name "unconnected-(U2F-LOGIC_VDD_7-PadU18)") (class "Default")
      (node (ref "U2") (pin "U18") (pinfunction "LOGIC_VDD_7_U18") (pintype "power_in"))
    )
    (net (code "31") (name "unconnected-(U2F-LOGIC_VDD_8-PadU17)") (class "Default")
      (node (ref "U2") (pin "U17") (pinfunction "LOGIC_VDD_8_U17") (pintype "power_in"))
    )
    (net (code "32") (name "unconnected-(U2F-LOGIC_VDD_9-PadM17)") (class "Default")
      (node (ref "U2") (pin "M17") (pinfunction "LOGIC_VDD_9_M17") (pintype "power_in"))
    )
    (net (code "33") (name "unconnected-(U2F-LOGIC_VDD_10-PadL17)") (class "Default")
      (node (ref "U2") (pin "L17") (pinfunction "LOGIC_VDD_10_L17") (pintype "power_in"))
    )
    (net (code "34") (name "unconnected-(U2F-LOGIC_VDD_11-PadT17)") (class "Default")
      (node (ref "U2") (pin "T17") (pinfunction "LOGIC_VDD_11_T17") (pintype "power_in"))
    )
    (net (code "35") (name "unconnected-(U2F-LOGIC_VDD_12-PadU20)") (class "Default")
      (node (ref "U2") (pin "U20") (pinfunction "LOGIC_VDD_12_U20") (pintype "power_in"))
    )
  )
)
